# people-counter-74xx.net
KiCad netlist of a schematic drawn in EAGLE
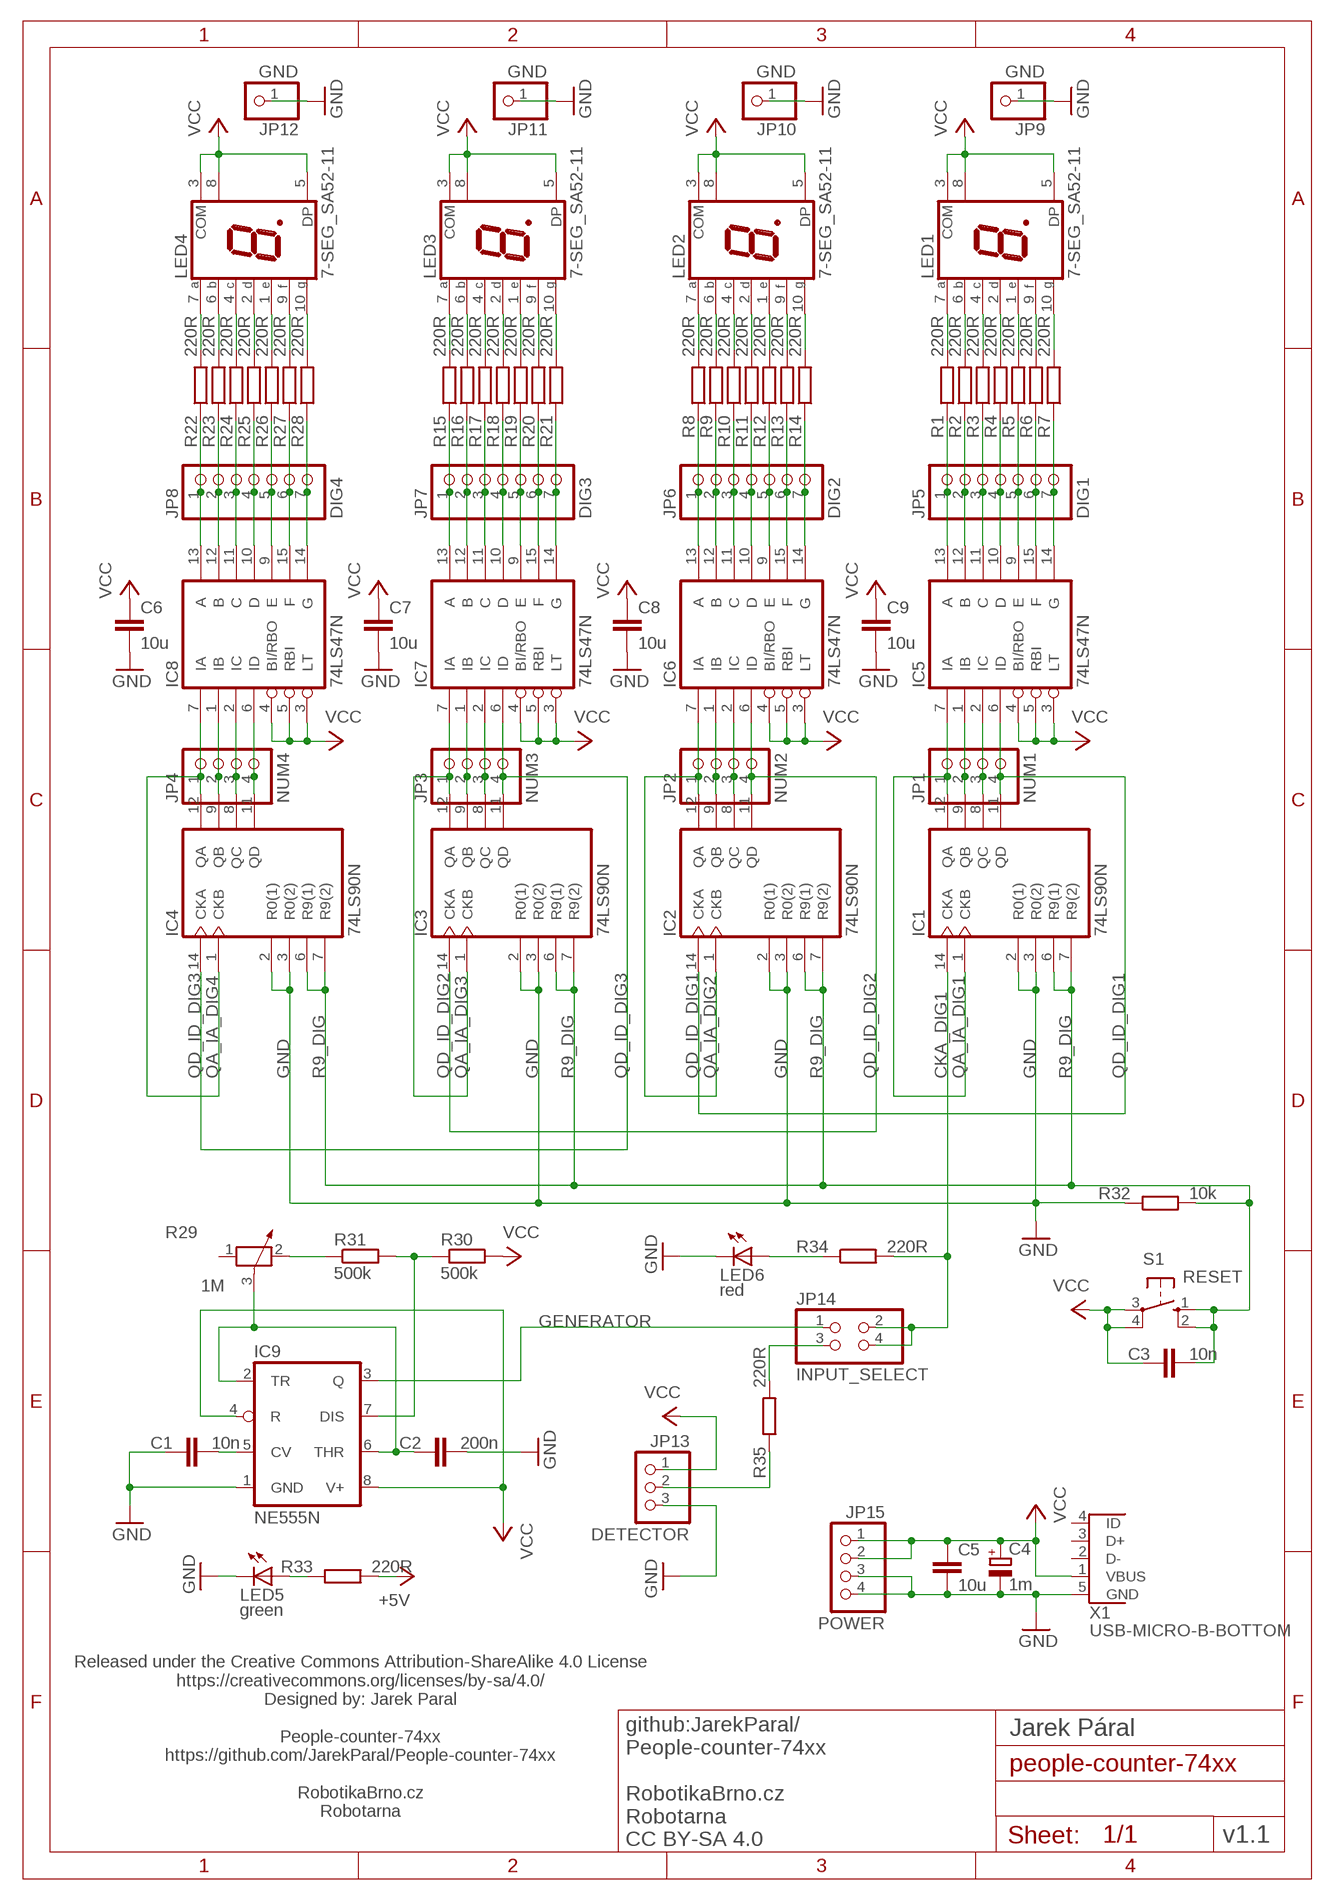
[diagram p0: schematic, sheet 1]

(export (version "E")
  (design (tool "Eeschema 10.0.6"))
  (components
    (comp (ref "C1")
      (value "10n")
      (footprint "eagle-import:C0603")
      (libsource (lib "eagle-import") (part "C-EUC0603"))
    )
    (comp (ref "C2")
      (value "200n")
      (footprint "eagle-import:C0805")
      (libsource (lib "eagle-import") (part "C-EUC0805"))
    )
    (comp (ref "C3")
      (value "10n")
      (footprint "eagle-import:C0603")
      (libsource (lib "eagle-import") (part "C-EUC0603"))
    )
    (comp (ref "C4")
      (value "1m")
      (footprint "eagle-import:E5-10,5")
      (libsource (lib "eagle-import") (part "CPOL-EUE5-10.5"))
    )
    (comp (ref "C5")
      (value "10u")
      (footprint "eagle-import:C0805")
      (libsource (lib "eagle-import") (part "C-EUC0805"))
    )
    (comp (ref "C6")
      (value "10u")
      (footprint "eagle-import:C0805")
      (libsource (lib "eagle-import") (part "C-EUC0805"))
    )
    (comp (ref "C7")
      (value "10u")
      (footprint "eagle-import:C0805")
      (libsource (lib "eagle-import") (part "C-EUC0805"))
    )
    (comp (ref "C8")
      (value "10u")
      (footprint "eagle-import:C0805")
      (libsource (lib "eagle-import") (part "C-EUC0805"))
    )
    (comp (ref "C9")
      (value "10u")
      (footprint "eagle-import:C0805")
      (libsource (lib "eagle-import") (part "C-EUC0805"))
    )
    (comp (ref "IC1")
      (value "74LS90N")
      (footprint "eagle-import:DIL14")
      (libsource (lib "eagle-import") (part "7490NLS"))
    )
    (comp (ref "IC2")
      (value "74LS90N")
      (footprint "eagle-import:DIL14")
      (libsource (lib "eagle-import") (part "7490NLS"))
    )
    (comp (ref "IC3")
      (value "74LS90N")
      (footprint "eagle-import:DIL14")
      (libsource (lib "eagle-import") (part "7490NLS"))
    )
    (comp (ref "IC4")
      (value "74LS90N")
      (footprint "eagle-import:DIL14")
      (libsource (lib "eagle-import") (part "7490NLS"))
    )
    (comp (ref "IC5")
      (value "74LS47N")
      (footprint "eagle-import:DIL16")
      (libsource (lib "eagle-import") (part "7447NLS"))
    )
    (comp (ref "IC6")
      (value "74LS47N")
      (footprint "eagle-import:DIL16")
      (libsource (lib "eagle-import") (part "7447NLS"))
    )
    (comp (ref "IC7")
      (value "74LS47N")
      (footprint "eagle-import:DIL16")
      (libsource (lib "eagle-import") (part "7447NLS"))
    )
    (comp (ref "IC8")
      (value "74LS47N")
      (footprint "eagle-import:DIL16")
      (libsource (lib "eagle-import") (part "7447NLS"))
    )
    (comp (ref "IC9")
      (value "NE555N")
      (footprint "eagle-import:DIL08")
      (libsource (lib "eagle-import") (part "555NNE"))
    )
    (comp (ref "JP1")
      (value "NUM1")
      (footprint "eagle-import:1X04")
      (libsource (lib "eagle-import") (part "PINHD-1X4"))
    )
    (comp (ref "JP2")
      (value "NUM2")
      (footprint "eagle-import:1X04")
      (libsource (lib "eagle-import") (part "PINHD-1X4"))
    )
    (comp (ref "JP3")
      (value "NUM3")
      (footprint "eagle-import:1X04")
      (libsource (lib "eagle-import") (part "PINHD-1X4"))
    )
    (comp (ref "JP4")
      (value "NUM4")
      (footprint "eagle-import:1X04")
      (libsource (lib "eagle-import") (part "PINHD-1X4"))
    )
    (comp (ref "JP5")
      (value "DIG1")
      (footprint "eagle-import:1X07")
      (libsource (lib "eagle-import") (part "PINHD-1X7"))
    )
    (comp (ref "JP6")
      (value "DIG2")
      (footprint "eagle-import:1X07")
      (libsource (lib "eagle-import") (part "PINHD-1X7"))
    )
    (comp (ref "JP7")
      (value "DIG3")
      (footprint "eagle-import:1X07")
      (libsource (lib "eagle-import") (part "PINHD-1X7"))
    )
    (comp (ref "JP8")
      (value "DIG4")
      (footprint "eagle-import:1X07")
      (libsource (lib "eagle-import") (part "PINHD-1X7"))
    )
    (comp (ref "JP9")
      (value "GND")
      (footprint "eagle-import:1X01")
      (libsource (lib "eagle-import") (part "PINHD-1X1"))
    )
    (comp (ref "JP10")
      (value "GND")
      (footprint "eagle-import:1X01")
      (libsource (lib "eagle-import") (part "PINHD-1X1"))
    )
    (comp (ref "JP11")
      (value "GND")
      (footprint "eagle-import:1X01")
      (libsource (lib "eagle-import") (part "PINHD-1X1"))
    )
    (comp (ref "JP12")
      (value "GND")
      (footprint "eagle-import:1X01")
      (libsource (lib "eagle-import") (part "PINHD-1X1"))
    )
    (comp (ref "JP13")
      (value "DETECTOR")
      (footprint "eagle-import:1X03_90")
      (libsource (lib "eagle-import") (part "PINHD-1X3/90"))
    )
    (comp (ref "JP14")
      (value "INPUT_SELECT")
      (footprint "eagle-import:2X02")
      (libsource (lib "eagle-import") (part "PINHD-2X2"))
    )
    (comp (ref "JP15")
      (value "POWER")
      (footprint "eagle-import:1X04_90")
      (libsource (lib "eagle-import") (part "PINHD-1X4/90"))
    )
    (comp (ref "LED1")
      (value "7-SEG_SA52-11")
      (footprint "eagle-import:SA52-11")
      (libsource (lib "eagle-import") (part "7-SEG_SA52-11"))
    )
    (comp (ref "LED2")
      (value "7-SEG_SA52-11")
      (footprint "eagle-import:SA52-11")
      (libsource (lib "eagle-import") (part "7-SEG_SA52-11"))
    )
    (comp (ref "LED3")
      (value "7-SEG_SA52-11")
      (footprint "eagle-import:SA52-11")
      (libsource (lib "eagle-import") (part "7-SEG_SA52-11"))
    )
    (comp (ref "LED4")
      (value "7-SEG_SA52-11")
      (footprint "eagle-import:SA52-11")
      (libsource (lib "eagle-import") (part "7-SEG_SA52-11"))
    )
    (comp (ref "LED5")
      (value "green")
      (footprint "eagle-import:CHIPLED_0603")
      (libsource (lib "eagle-import") (part "LEDCHIPLED_0603"))
    )
    (comp (ref "LED6")
      (value "red")
      (footprint "eagle-import:CHIPLED_0603")
      (libsource (lib "eagle-import") (part "LEDCHIPLED_0603"))
    )
    (comp (ref "R1")
      (value "220R")
      (footprint "eagle-import:R0603")
      (libsource (lib "eagle-import") (part "R-EU_R0603"))
    )
    (comp (ref "R2")
      (value "220R")
      (footprint "eagle-import:R0603")
      (libsource (lib "eagle-import") (part "R-EU_R0603"))
    )
    (comp (ref "R3")
      (value "220R")
      (footprint "eagle-import:R0603")
      (libsource (lib "eagle-import") (part "R-EU_R0603"))
    )
    (comp (ref "R4")
      (value "220R")
      (footprint "eagle-import:R0603")
      (libsource (lib "eagle-import") (part "R-EU_R0603"))
    )
    (comp (ref "R5")
      (value "220R")
      (footprint "eagle-import:R0603")
      (libsource (lib "eagle-import") (part "R-EU_R0603"))
    )
    (comp (ref "R6")
      (value "220R")
      (footprint "eagle-import:R0603")
      (libsource (lib "eagle-import") (part "R-EU_R0603"))
    )
    (comp (ref "R7")
      (value "220R")
      (footprint "eagle-import:R0603")
      (libsource (lib "eagle-import") (part "R-EU_R0603"))
    )
    (comp (ref "R8")
      (value "220R")
      (footprint "eagle-import:R0603")
      (libsource (lib "eagle-import") (part "R-EU_R0603"))
    )
    (comp (ref "R9")
      (value "220R")
      (footprint "eagle-import:R0603")
      (libsource (lib "eagle-import") (part "R-EU_R0603"))
    )
    (comp (ref "R10")
      (value "220R")
      (footprint "eagle-import:R0603")
      (libsource (lib "eagle-import") (part "R-EU_R0603"))
    )
    (comp (ref "R11")
      (value "220R")
      (footprint "eagle-import:R0603")
      (libsource (lib "eagle-import") (part "R-EU_R0603"))
    )
    (comp (ref "R12")
      (value "220R")
      (footprint "eagle-import:R0603")
      (libsource (lib "eagle-import") (part "R-EU_R0603"))
    )
    (comp (ref "R13")
      (value "220R")
      (footprint "eagle-import:R0603")
      (libsource (lib "eagle-import") (part "R-EU_R0603"))
    )
    (comp (ref "R14")
      (value "220R")
      (footprint "eagle-import:R0603")
      (libsource (lib "eagle-import") (part "R-EU_R0603"))
    )
    (comp (ref "R15")
      (value "220R")
      (footprint "eagle-import:R0603")
      (libsource (lib "eagle-import") (part "R-EU_R0603"))
    )
    (comp (ref "R16")
      (value "220R")
      (footprint "eagle-import:R0603")
      (libsource (lib "eagle-import") (part "R-EU_R0603"))
    )
    (comp (ref "R17")
      (value "220R")
      (footprint "eagle-import:R0603")
      (libsource (lib "eagle-import") (part "R-EU_R0603"))
    )
    (comp (ref "R18")
      (value "220R")
      (footprint "eagle-import:R0603")
      (libsource (lib "eagle-import") (part "R-EU_R0603"))
    )
    (comp (ref "R19")
      (value "220R")
      (footprint "eagle-import:R0603")
      (libsource (lib "eagle-import") (part "R-EU_R0603"))
    )
    (comp (ref "R20")
      (value "220R")
      (footprint "eagle-import:R0603")
      (libsource (lib "eagle-import") (part "R-EU_R0603"))
    )
    (comp (ref "R21")
      (value "220R")
      (footprint "eagle-import:R0603")
      (libsource (lib "eagle-import") (part "R-EU_R0603"))
    )
    (comp (ref "R22")
      (value "220R")
      (footprint "eagle-import:R0603")
      (libsource (lib "eagle-import") (part "R-EU_R0603"))
    )
    (comp (ref "R23")
      (value "220R")
      (footprint "eagle-import:R0603")
      (libsource (lib "eagle-import") (part "R-EU_R0603"))
    )
    (comp (ref "R24")
      (value "220R")
      (footprint "eagle-import:R0603")
      (libsource (lib "eagle-import") (part "R-EU_R0603"))
    )
    (comp (ref "R25")
      (value "220R")
      (footprint "eagle-import:R0603")
      (libsource (lib "eagle-import") (part "R-EU_R0603"))
    )
    (comp (ref "R26")
      (value "220R")
      (footprint "eagle-import:R0603")
      (libsource (lib "eagle-import") (part "R-EU_R0603"))
    )
    (comp (ref "R27")
      (value "220R")
      (footprint "eagle-import:R0603")
      (libsource (lib "eagle-import") (part "R-EU_R0603"))
    )
    (comp (ref "R28")
      (value "220R")
      (footprint "eagle-import:R0603")
      (libsource (lib "eagle-import") (part "R-EU_R0603"))
    )
    (comp (ref "R29")
      (value "1M")
      (footprint "eagle-import:PT-10")
      (libsource (lib "eagle-import") (part "POTENTIOMETER_PT-10"))
    )
    (comp (ref "R30")
      (value "500k")
      (footprint "eagle-import:R0603")
      (libsource (lib "eagle-import") (part "R-EU_R0603"))
    )
    (comp (ref "R31")
      (value "500k")
      (footprint "eagle-import:R0603")
      (libsource (lib "eagle-import") (part "R-EU_R0603"))
    )
    (comp (ref "R32")
      (value "10k")
      (footprint "eagle-import:R0603")
      (libsource (lib "eagle-import") (part "R-EU_R0603"))
    )
    (comp (ref "R33")
      (value "220R")
      (footprint "eagle-import:R0603")
      (libsource (lib "eagle-import") (part "R-EU_R0603"))
    )
    (comp (ref "R34")
      (value "220R")
      (footprint "eagle-import:R0603")
      (libsource (lib "eagle-import") (part "R-EU_R0603"))
    )
    (comp (ref "R35")
      (value "220R")
      (footprint "eagle-import:R0603")
      (libsource (lib "eagle-import") (part "R-EU_R0603"))
    )
    (comp (ref "S1")
      (value "RESET")
      (footprint "eagle-import:B3F-10XX")
      (fields (field (name "MPN") "B3F-1000"))
      (libsource (lib "eagle-import") (part "10-XX"))
    )
    (comp (ref "X1")
      (value "USB-MICRO-B-BOTTOM")
      (footprint "eagle-import:USB-MICRO-B-BOTTOM-MOLEX")
      (libsource (lib "eagle-import") (part "USB-MICRO-B-BOTTOM"))
    )
  )
  (nets
    (net (code "1") (name "+5V") (class "Default")
      (node (ref "R33") (pin "2") (pinfunction "2_2") (pintype "passive"))
    )
    (net (code "2") (name "/CKA_DIG1") (class "Default")
      (node (ref "IC1") (pin "14") (pinfunction "CKA_14") (pintype "input"))
      (node (ref "JP14") (pin "2") (pinfunction "2_2") (pintype "passive"))
      (node (ref "JP14") (pin "4") (pinfunction "4_4") (pintype "passive"))
      (node (ref "R34") (pin "2") (pinfunction "2_2") (pintype "passive"))
    )
    (net (code "3") (name "/GENERATOR") (class "Default")
      (node (ref "IC9") (pin "3") (pinfunction "Q_3") (pintype "output"))
      (node (ref "JP14") (pin "1") (pinfunction "1_1") (pintype "passive"))
    )
    (net (code "4") (name "/QA_IA_DIG1") (class "Default")
      (node (ref "IC1") (pin "1") (pinfunction "CKB_1") (pintype "input"))
      (node (ref "IC1") (pin "12") (pinfunction "QA_12") (pintype "output"))
      (node (ref "IC5") (pin "7") (pinfunction "IA_7") (pintype "input"))
      (node (ref "JP1") (pin "1") (pinfunction "1_1") (pintype "passive"))
    )
    (net (code "5") (name "/QA_IA_DIG2") (class "Default")
      (node (ref "IC2") (pin "1") (pinfunction "CKB_1") (pintype "input"))
      (node (ref "IC2") (pin "12") (pinfunction "QA_12") (pintype "output"))
      (node (ref "IC6") (pin "7") (pinfunction "IA_7") (pintype "input"))
      (node (ref "JP2") (pin "1") (pinfunction "1_1") (pintype "passive"))
    )
    (net (code "6") (name "/QA_IA_DIG3") (class "Default")
      (node (ref "IC3") (pin "1") (pinfunction "CKB_1") (pintype "input"))
      (node (ref "IC3") (pin "12") (pinfunction "QA_12") (pintype "output"))
      (node (ref "IC7") (pin "7") (pinfunction "IA_7") (pintype "input"))
      (node (ref "JP3") (pin "1") (pinfunction "1_1") (pintype "passive"))
    )
    (net (code "7") (name "/QA_IA_DIG4") (class "Default")
      (node (ref "IC4") (pin "1") (pinfunction "CKB_1") (pintype "input"))
      (node (ref "IC4") (pin "12") (pinfunction "QA_12") (pintype "output"))
      (node (ref "IC8") (pin "7") (pinfunction "IA_7") (pintype "input"))
      (node (ref "JP4") (pin "1") (pinfunction "1_1") (pintype "passive"))
    )
    (net (code "8") (name "/QD_ID_DIG1") (class "Default")
      (node (ref "IC1") (pin "11") (pinfunction "QD_11") (pintype "output"))
      (node (ref "IC2") (pin "14") (pinfunction "CKA_14") (pintype "input"))
      (node (ref "IC5") (pin "6") (pinfunction "ID_6") (pintype "input"))
      (node (ref "JP1") (pin "4") (pinfunction "4_4") (pintype "passive"))
    )
    (net (code "9") (name "/QD_ID_DIG2") (class "Default")
      (node (ref "IC2") (pin "11") (pinfunction "QD_11") (pintype "output"))
      (node (ref "IC3") (pin "14") (pinfunction "CKA_14") (pintype "input"))
      (node (ref "IC6") (pin "6") (pinfunction "ID_6") (pintype "input"))
      (node (ref "JP2") (pin "4") (pinfunction "4_4") (pintype "passive"))
    )
    (net (code "10") (name "/QD_ID_DIG3") (class "Default")
      (node (ref "IC3") (pin "11") (pinfunction "QD_11") (pintype "output"))
      (node (ref "IC4") (pin "14") (pinfunction "CKA_14") (pintype "input"))
      (node (ref "IC7") (pin "6") (pinfunction "ID_6") (pintype "input"))
      (node (ref "JP3") (pin "4") (pinfunction "4_4") (pintype "passive"))
    )
    (net (code "11") (name "/R9_DIG") (class "Default")
      (node (ref "C3") (pin "2") (pinfunction "2_2") (pintype "passive"))
      (node (ref "IC1") (pin "6") (pinfunction "R9(1)_6") (pintype "input"))
      (node (ref "IC1") (pin "7") (pinfunction "R9(2)_7") (pintype "input"))
      (node (ref "IC2") (pin "6") (pinfunction "R9(1)_6") (pintype "input"))
      (node (ref "IC2") (pin "7") (pinfunction "R9(2)_7") (pintype "input"))
      (node (ref "IC3") (pin "6") (pinfunction "R9(1)_6") (pintype "input"))
      (node (ref "IC3") (pin "7") (pinfunction "R9(2)_7") (pintype "input"))
      (node (ref "IC4") (pin "6") (pinfunction "R9(1)_6") (pintype "input"))
      (node (ref "IC4") (pin "7") (pinfunction "R9(2)_7") (pintype "input"))
      (node (ref "R32") (pin "2") (pinfunction "2_2") (pintype "passive"))
      (node (ref "S1") (pin "1") (pinfunction "S_1") (pintype "passive"))
      (node (ref "S1") (pin "2") (pinfunction "S1_2") (pintype "passive"))
    )
    (net (code "12") (name "GND") (class "Default")
      (node (ref "C1") (pin "1") (pinfunction "1_1") (pintype "passive"))
      (node (ref "C2") (pin "2") (pinfunction "2_2") (pintype "passive"))
      (node (ref "C4") (pin "-") (pinfunction "-_-") (pintype "passive"))
      (node (ref "C5") (pin "2") (pinfunction "2_2") (pintype "passive"))
      (node (ref "C6") (pin "2") (pinfunction "2_2") (pintype "passive"))
      (node (ref "C7") (pin "2") (pinfunction "2_2") (pintype "passive"))
      (node (ref "C8") (pin "2") (pinfunction "2_2") (pintype "passive"))
      (node (ref "C9") (pin "2") (pinfunction "2_2") (pintype "passive"))
      (node (ref "IC1") (pin "2") (pinfunction "R0(1)_2") (pintype "input"))
      (node (ref "IC1") (pin "3") (pinfunction "R0(2)_3") (pintype "input"))
      (node (ref "IC2") (pin "2") (pinfunction "R0(1)_2") (pintype "input"))
      (node (ref "IC2") (pin "3") (pinfunction "R0(2)_3") (pintype "input"))
      (node (ref "IC3") (pin "2") (pinfunction "R0(1)_2") (pintype "input"))
      (node (ref "IC3") (pin "3") (pinfunction "R0(2)_3") (pintype "input"))
      (node (ref "IC4") (pin "2") (pinfunction "R0(1)_2") (pintype "input"))
      (node (ref "IC4") (pin "3") (pinfunction "R0(2)_3") (pintype "input"))
      (node (ref "IC9") (pin "1") (pinfunction "GND_1") (pintype "power_in"))
      (node (ref "JP10") (pin "1") (pinfunction "1_1") (pintype "passive"))
      (node (ref "JP11") (pin "1") (pinfunction "1_1") (pintype "passive"))
      (node (ref "JP12") (pin "1") (pinfunction "1_1") (pintype "passive"))
      (node (ref "JP13") (pin "3") (pinfunction "3_3") (pintype "passive"))
      (node (ref "JP15") (pin "3") (pinfunction "3_3") (pintype "passive"))
      (node (ref "JP15") (pin "4") (pinfunction "4_4") (pintype "passive"))
      (node (ref "JP9") (pin "1") (pinfunction "1_1") (pintype "passive"))
      (node (ref "LED5") (pin "C") (pinfunction "C_C") (pintype "passive"))
      (node (ref "LED6") (pin "C") (pinfunction "C_C") (pintype "passive"))
      (node (ref "R32") (pin "1") (pinfunction "1_1") (pintype "passive"))
      (node (ref "X1") (pin "5") (pinfunction "GND_5") (pintype "passive"))
    )
    (net (code "13") (name "Net-(IC1A-QB)") (class "Default")
      (node (ref "IC1") (pin "9") (pinfunction "QB_9") (pintype "output"))
      (node (ref "IC5") (pin "1") (pinfunction "IB_1") (pintype "input"))
      (node (ref "JP1") (pin "2") (pinfunction "2_2") (pintype "passive"))
    )
    (net (code "14") (name "Net-(IC1A-QC)") (class "Default")
      (node (ref "IC1") (pin "8") (pinfunction "QC_8") (pintype "output"))
      (node (ref "IC5") (pin "2") (pinfunction "IC_2") (pintype "input"))
      (node (ref "JP1") (pin "3") (pinfunction "3_3") (pintype "passive"))
    )
    (net (code "15") (name "Net-(IC2A-QB)") (class "Default")
      (node (ref "IC2") (pin "9") (pinfunction "QB_9") (pintype "output"))
      (node (ref "IC6") (pin "1") (pinfunction "IB_1") (pintype "input"))
      (node (ref "JP2") (pin "2") (pinfunction "2_2") (pintype "passive"))
    )
    (net (code "16") (name "Net-(IC2A-QC)") (class "Default")
      (node (ref "IC2") (pin "8") (pinfunction "QC_8") (pintype "output"))
      (node (ref "IC6") (pin "2") (pinfunction "IC_2") (pintype "input"))
      (node (ref "JP2") (pin "3") (pinfunction "3_3") (pintype "passive"))
    )
    (net (code "17") (name "Net-(IC3A-QB)") (class "Default")
      (node (ref "IC3") (pin "9") (pinfunction "QB_9") (pintype "output"))
      (node (ref "IC7") (pin "1") (pinfunction "IB_1") (pintype "input"))
      (node (ref "JP3") (pin "2") (pinfunction "2_2") (pintype "passive"))
    )
    (net (code "18") (name "Net-(IC3A-QC)") (class "Default")
      (node (ref "IC3") (pin "8") (pinfunction "QC_8") (pintype "output"))
      (node (ref "IC7") (pin "2") (pinfunction "IC_2") (pintype "input"))
      (node (ref "JP3") (pin "3") (pinfunction "3_3") (pintype "passive"))
    )
    (net (code "19") (name "Net-(IC4A-QB)") (class "Default")
      (node (ref "IC4") (pin "9") (pinfunction "QB_9") (pintype "output"))
      (node (ref "IC8") (pin "1") (pinfunction "IB_1") (pintype "input"))
      (node (ref "JP4") (pin "2") (pinfunction "2_2") (pintype "passive"))
    )
    (net (code "20") (name "Net-(IC4A-QC)") (class "Default")
      (node (ref "IC4") (pin "8") (pinfunction "QC_8") (pintype "output"))
      (node (ref "IC8") (pin "2") (pinfunction "IC_2") (pintype "input"))
      (node (ref "JP4") (pin "3") (pinfunction "3_3") (pintype "passive"))
    )
    (net (code "21") (name "Net-(IC4A-QD)") (class "Default")
      (node (ref "IC4") (pin "11") (pinfunction "QD_11") (pintype "output"))
      (node (ref "IC8") (pin "6") (pinfunction "ID_6") (pintype "input"))
      (node (ref "JP4") (pin "4") (pinfunction "4_4") (pintype "passive"))
    )
    (net (code "22") (name "Net-(IC5A-A)") (class "Default")
      (node (ref "IC5") (pin "13") (pinfunction "A_13") (pintype "output"))
      (node (ref "JP5") (pin "1") (pinfunction "1_1") (pintype "passive"))
      (node (ref "R1") (pin "1") (pinfunction "1_1") (pintype "passive"))
    )
    (net (code "23") (name "Net-(IC5A-B)") (class "Default")
      (node (ref "IC5") (pin "12") (pinfunction "B_12") (pintype "output"))
      (node (ref "JP5") (pin "2") (pinfunction "2_2") (pintype "passive"))
      (node (ref "R2") (pin "1") (pinfunction "1_1") (pintype "passive"))
    )
    (net (code "24") (name "Net-(IC5A-C)") (class "Default")
      (node (ref "IC5") (pin "11") (pinfunction "C_11") (pintype "output"))
      (node (ref "JP5") (pin "3") (pinfunction "3_3") (pintype "passive"))
      (node (ref "R3") (pin "1") (pinfunction "1_1") (pintype "passive"))
    )
    (net (code "25") (name "Net-(IC5A-D)") (class "Default")
      (node (ref "IC5") (pin "10") (pinfunction "D_10") (pintype "output"))
      (node (ref "JP5") (pin "4") (pinfunction "4_4") (pintype "passive"))
      (node (ref "R4") (pin "1") (pinfunction "1_1") (pintype "passive"))
    )
    (net (code "26") (name "Net-(IC5A-E)") (class "Default")
      (node (ref "IC5") (pin "9") (pinfunction "E_9") (pintype "output"))
      (node (ref "JP5") (pin "5") (pinfunction "5_5") (pintype "passive"))
      (node (ref "R5") (pin "1") (pinfunction "1_1") (pintype "passive"))
    )
    (net (code "27") (name "Net-(IC5A-F)") (class "Default")
      (node (ref "IC5") (pin "15") (pinfunction "F_15") (pintype "output"))
      (node (ref "JP5") (pin "6") (pinfunction "6_6") (pintype "passive"))
      (node (ref "R6") (pin "1") (pinfunction "1_1") (pintype "passive"))
    )
    (net (code "28") (name "Net-(IC5A-G)") (class "Default")
      (node (ref "IC5") (pin "14") (pinfunction "G_14") (pintype "output"))
      (node (ref "JP5") (pin "7") (pinfunction "7_7") (pintype "passive"))
      (node (ref "R7") (pin "1") (pinfunction "1_1") (pintype "passive"))
    )
    (net (code "29") (name "Net-(IC6A-A)") (class "Default")
      (node (ref "IC6") (pin "13") (pinfunction "A_13") (pintype "output"))
      (node (ref "JP6") (pin "1") (pinfunction "1_1") (pintype "passive"))
      (node (ref "R8") (pin "1") (pinfunction "1_1") (pintype "passive"))
    )
    (net (code "30") (name "Net-(IC6A-B)") (class "Default")
      (node (ref "IC6") (pin "12") (pinfunction "B_12") (pintype "output"))
      (node (ref "JP6") (pin "2") (pinfunction "2_2") (pintype "passive"))
      (node (ref "R9") (pin "1") (pinfunction "1_1") (pintype "passive"))
    )
    (net (code "31") (name "Net-(IC6A-C)") (class "Default")
      (node (ref "IC6") (pin "11") (pinfunction "C_11") (pintype "output"))
      (node (ref "JP6") (pin "3") (pinfunction "3_3") (pintype "passive"))
      (node (ref "R10") (pin "1") (pinfunction "1_1") (pintype "passive"))
    )
    (net (code "32") (name "Net-(IC6A-D)") (class "Default")
      (node (ref "IC6") (pin "10") (pinfunction "D_10") (pintype "output"))
      (node (ref "JP6") (pin "4") (pinfunction "4_4") (pintype "passive"))
      (node (ref "R11") (pin "1") (pinfunction "1_1") (pintype "passive"))
    )
    (net (code "33") (name "Net-(IC6A-E)") (class "Default")
      (node (ref "IC6") (pin "9") (pinfunction "E_9") (pintype "output"))
      (node (ref "JP6") (pin "5") (pinfunction "5_5") (pintype "passive"))
      (node (ref "R12") (pin "1") (pinfunction "1_1") (pintype "passive"))
    )
    (net (code "34") (name "Net-(IC6A-F)") (class "Default")
      (node (ref "IC6") (pin "15") (pinfunction "F_15") (pintype "output"))
      (node (ref "JP6") (pin "6") (pinfunction "6_6") (pintype "passive"))
      (node (ref "R13") (pin "1") (pinfunction "1_1") (pintype "passive"))
    )
    (net (code "35") (name "Net-(IC6A-G)") (class "Default")
      (node (ref "IC6") (pin "14") (pinfunction "G_14") (pintype "output"))
      (node (ref "JP6") (pin "7") (pinfunction "7_7") (pintype "passive"))
      (node (ref "R14") (pin "1") (pinfunction "1_1") (pintype "passive"))
    )
    (net (code "36") (name "Net-(IC7A-A)") (class "Default")
      (node (ref "IC7") (pin "13") (pinfunction "A_13") (pintype "output"))
      (node (ref "JP7") (pin "1") (pinfunction "1_1") (pintype "passive"))
      (node (ref "R15") (pin "1") (pinfunction "1_1") (pintype "passive"))
    )
    (net (code "37") (name "Net-(IC7A-B)") (class "Default")
      (node (ref "IC7") (pin "12") (pinfunction "B_12") (pintype "output"))
      (node (ref "JP7") (pin "2") (pinfunction "2_2") (pintype "passive"))
      (node (ref "R16") (pin "1") (pinfunction "1_1") (pintype "passive"))
    )
    (net (code "38") (name "Net-(IC7A-C)") (class "Default")
      (node (ref "IC7") (pin "11") (pinfunction "C_11") (pintype "output"))
      (node (ref "JP7") (pin "3") (pinfunction "3_3") (pintype "passive"))
      (node (ref "R17") (pin "1") (pinfunction "1_1") (pintype "passive"))
    )
    (net (code "39") (name "Net-(IC7A-D)") (class "Default")
      (node (ref "IC7") (pin "10") (pinfunction "D_10") (pintype "output"))
      (node (ref "JP7") (pin "4") (pinfunction "4_4") (pintype "passive"))
      (node (ref "R18") (pin "1") (pinfunction "1_1") (pintype "passive"))
    )
    (net (code "40") (name "Net-(IC7A-E)") (class "Default")
      (node (ref "IC7") (pin "9") (pinfunction "E_9") (pintype "output"))
      (node (ref "JP7") (pin "5") (pinfunction "5_5") (pintype "passive"))
      (node (ref "R19") (pin "1") (pinfunction "1_1") (pintype "passive"))
    )
    (net (code "41") (name "Net-(IC7A-F)") (class "Default")
      (node (ref "IC7") (pin "15") (pinfunction "F_15") (pintype "output"))
      (node (ref "JP7") (pin "6") (pinfunction "6_6") (pintype "passive"))
      (node (ref "R20") (pin "1") (pinfunction "1_1") (pintype "passive"))
    )
    (net (code "42") (name "Net-(IC7A-G)") (class "Default")
      (node (ref "IC7") (pin "14") (pinfunction "G_14") (pintype "output"))
      (node (ref "JP7") (pin "7") (pinfunction "7_7") (pintype "passive"))
      (node (ref "R21") (pin "1") (pinfunction "1_1") (pintype "passive"))
    )
    (net (code "43") (name "Net-(IC8A-A)") (class "Default")
      (node (ref "IC8") (pin "13") (pinfunction "A_13") (pintype "output"))
      (node (ref "JP8") (pin "1") (pinfunction "1_1") (pintype "passive"))
      (node (ref "R22") (pin "1") (pinfunction "1_1") (pintype "passive"))
    )
    (net (code "44") (name "Net-(IC8A-B)") (class "Default")
      (node (ref "IC8") (pin "12") (pinfunction "B_12") (pintype "output"))
      (node (ref "JP8") (pin "2") (pinfunction "2_2") (pintype "passive"))
      (node (ref "R23") (pin "1") (pinfunction "1_1") (pintype "passive"))
    )
    (net (code "45") (name "Net-(IC8A-C)") (class "Default")
      (node (ref "IC8") (pin "11") (pinfunction "C_11") (pintype "output"))
      (node (ref "JP8") (pin "3") (pinfunction "3_3") (pintype "passive"))
      (node (ref "R24") (pin "1") (pinfunction "1_1") (pintype "passive"))
    )
    (net (code "46") (name "Net-(IC8A-D)") (class "Default")
      (node (ref "IC8") (pin "10") (pinfunction "D_10") (pintype "output"))
      (node (ref "JP8") (pin "4") (pinfunction "4_4") (pintype "passive"))
      (node (ref "R25") (pin "1") (pinfunction "1_1") (pintype "passive"))
    )
    (net (code "47") (name "Net-(IC8A-E)") (class "Default")
      (node (ref "IC8") (pin "9") (pinfunction "E_9") (pintype "output"))
      (node (ref "JP8") (pin "5") (pinfunction "5_5") (pintype "passive"))
      (node (ref "R26") (pin "1") (pinfunction "1_1") (pintype "passive"))
    )
    (net (code "48") (name "Net-(IC8A-F)") (class "Default")
      (node (ref "IC8") (pin "15") (pinfunction "F_15") (pintype "output"))
      (node (ref "JP8") (pin "6") (pinfunction "6_6") (pintype "passive"))
      (node (ref "R27") (pin "1") (pinfunction "1_1") (pintype "passive"))
    )
    (net (code "49") (name "Net-(IC8A-G)") (class "Default")
      (node (ref "IC8") (pin "14") (pinfunction "G_14") (pintype "output"))
      (node (ref "JP8") (pin "7") (pinfunction "7_7") (pintype "passive"))
      (node (ref "R28") (pin "1") (pinfunction "1_1") (pintype "passive"))
    )
    (net (code "50") (name "Net-(IC9-CV)") (class "Default")
      (node (ref "C1") (pin "2") (pinfunction "2_2") (pintype "passive"))
      (node (ref "IC9") (pin "5") (pinfunction "CV_5") (pintype "input"))
    )
    (net (code "51") (name "Net-(IC9-DIS)") (class "Default")
      (node (ref "IC9") (pin "7") (pinfunction "DIS_7") (pintype "input"))
      (node (ref "R30") (pin "1") (pinfunction "1_1") (pintype "passive"))
      (node (ref "R31") (pin "2") (pinfunction "2_2") (pintype "passive"))
    )
    (net (code "52") (name "Net-(IC9-THR)") (class "Default")
      (node (ref "C2") (pin "1") (pinfunction "1_1") (pintype "passive"))
      (node (ref "IC9") (pin "2") (pinfunction "TR_2") (pintype "input"))
      (node (ref "IC9") (pin "6") (pinfunction "THR_6") (pintype "input"))
      (node (ref "R29") (pin "3") (pinfunction "3_3") (pintype "passive"))
    )
    (net (code "53") (name "Net-(JP13-Pad2)") (class "Default")
      (node (ref "JP13") (pin "2") (pinfunction "2_2") (pintype "passive"))
      (node (ref "R35") (pin "1") (pinfunction "1_1") (pintype "passive"))
    )
    (net (code "54") (name "Net-(JP14-Pad3)") (class "Default")
      (node (ref "JP14") (pin "3") (pinfunction "3_3") (pintype "passive"))
      (node (ref "R35") (pin "2") (pinfunction "2_2") (pintype "passive"))
    )
    (net (code "55") (name "Net-(LED1-A)") (class "Default")
      (node (ref "LED1") (pin "7") (pinfunction "A_7") (pintype "passive"))
      (node (ref "R1") (pin "2") (pinfunction "2_2") (pintype "passive"))
    )
    (net (code "56") (name "Net-(LED1-B)") (class "Default")
      (node (ref "LED1") (pin "6") (pinfunction "B_6") (pintype "passive"))
      (node (ref "R2") (pin "2") (pinfunction "2_2") (pintype "passive"))
    )
    (net (code "57") (name "Net-(LED1-C)") (class "Default")
      (node (ref "LED1") (pin "4") (pinfunction "C_4") (pintype "passive"))
      (node (ref "R3") (pin "2") (pinfunction "2_2") (pintype "passive"))
    )
    (net (code "58") (name "Net-(LED1-D)") (class "Default")
      (node (ref "LED1") (pin "2") (pinfunction "D_2") (pintype "passive"))
      (node (ref "R4") (pin "2") (pinfunction "2_2") (pintype "passive"))
    )
    (net (code "59") (name "Net-(LED1-E)") (class "Default")
      (node (ref "LED1") (pin "1") (pinfunction "E_1") (pintype "passive"))
      (node (ref "R5") (pin "2") (pinfunction "2_2") (pintype "passive"))
    )
    (net (code "60") (name "Net-(LED1-F)") (class "Default")
      (node (ref "LED1") (pin "9") (pinfunction "F_9") (pintype "passive"))
      (node (ref "R6") (pin "2") (pinfunction "2_2") (pintype "passive"))
    )
    (net (code "61") (name "Net-(LED1-G)") (class "Default")
      (node (ref "LED1") (pin "10") (pinfunction "G_10") (pintype "passive"))
      (node (ref "R7") (pin "2") (pinfunction "2_2") (pintype "passive"))
    )
    (net (code "62") (name "Net-(LED2-A)") (class "Default")
      (node (ref "LED2") (pin "7") (pinfunction "A_7") (pintype "passive"))
      (node (ref "R8") (pin "2") (pinfunction "2_2") (pintype "passive"))
    )
    (net (code "63") (name "Net-(LED2-B)") (class "Default")
      (node (ref "LED2") (pin "6") (pinfunction "B_6") (pintype "passive"))
      (node (ref "R9") (pin "2") (pinfunction "2_2") (pintype "passive"))
    )
    (net (code "64") (name "Net-(LED2-C)") (class "Default")
      (node (ref "LED2") (pin "4") (pinfunction "C_4") (pintype "passive"))
      (node (ref "R10") (pin "2") (pinfunction "2_2") (pintype "passive"))
    )
    (net (code "65") (name "Net-(LED2-D)") (class "Default")
      (node (ref "LED2") (pin "2") (pinfunction "D_2") (pintype "passive"))
      (node (ref "R11") (pin "2") (pinfunction "2_2") (pintype "passive"))
    )
    (net (code "66") (name "Net-(LED2-E)") (class "Default")
      (node (ref "LED2") (pin "1") (pinfunction "E_1") (pintype "passive"))
      (node (ref "R12") (pin "2") (pinfunction "2_2") (pintype "passive"))
    )
    (net (code "67") (name "Net-(LED2-F)") (class "Default")
      (node (ref "LED2") (pin "9") (pinfunction "F_9") (pintype "passive"))
      (node (ref "R13") (pin "2") (pinfunction "2_2") (pintype "passive"))
    )
    (net (code "68") (name "Net-(LED2-G)") (class "Default")
      (node (ref "LED2") (pin "10") (pinfunction "G_10") (pintype "passive"))
      (node (ref "R14") (pin "2") (pinfunction "2_2") (pintype "passive"))
    )
    (net (code "69") (name "Net-(LED3-A)") (class "Default")
      (node (ref "LED3") (pin "7") (pinfunction "A_7") (pintype "passive"))
      (node (ref "R15") (pin "2") (pinfunction "2_2") (pintype "passive"))
    )
    (net (code "70") (name "Net-(LED3-B)") (class "Default")
      (node (ref "LED3") (pin "6") (pinfunction "B_6") (pintype "passive"))
      (node (ref "R16") (pin "2") (pinfunction "2_2") (pintype "passive"))
    )
    (net (code "71") (name "Net-(LED3-C)") (class "Default")
      (node (ref "LED3") (pin "4") (pinfunction "C_4") (pintype "passive"))
      (node (ref "R17") (pin "2") (pinfunction "2_2") (pintype "passive"))
    )
    (net (code "72") (name "Net-(LED3-D)") (class "Default")
      (node (ref "LED3") (pin "2") (pinfunction "D_2") (pintype "passive"))
      (node (ref "R18") (pin "2") (pinfunction "2_2") (pintype "passive"))
    )
    (net (code "73") (name "Net-(LED3-E)") (class "Default")
      (node (ref "LED3") (pin "1") (pinfunction "E_1") (pintype "passive"))
      (node (ref "R19") (pin "2") (pinfunction "2_2") (pintype "passive"))
    )
    (net (code "74") (name "Net-(LED3-F)") (class "Default")
      (node (ref "LED3") (pin "9") (pinfunction "F_9") (pintype "passive"))
      (node (ref "R20") (pin "2") (pinfunction "2_2") (pintype "passive"))
    )
    (net (code "75") (name "Net-(LED3-G)") (class "Default")
      (node (ref "LED3") (pin "10") (pinfunction "G_10") (pintype "passive"))
      (node (ref "R21") (pin "2") (pinfunction "2_2") (pintype "passive"))
    )
    (net (code "76") (name "Net-(LED4-A)") (class "Default")
      (node (ref "LED4") (pin "7") (pinfunction "A_7") (pintype "passive"))
      (node (ref "R22") (pin "2") (pinfunction "2_2") (pintype "passive"))
    )
    (net (code "77") (name "Net-(LED4-B)") (class "Default")
      (node (ref "LED4") (pin "6") (pinfunction "B_6") (pintype "passive"))
      (node (ref "R23") (pin "2") (pinfunction "2_2") (pintype "passive"))
    )
    (net (code "78") (name "Net-(LED4-C)") (class "Default")
      (node (ref "LED4") (pin "4") (pinfunction "C_4") (pintype "passive"))
      (node (ref "R24") (pin "2") (pinfunction "2_2") (pintype "passive"))
    )
    (net (code "79") (name "Net-(LED4-D)") (class "Default")
      (node (ref "LED4") (pin "2") (pinfunction "D_2") (pintype "passive"))
      (node (ref "R25") (pin "2") (pinfunction "2_2") (pintype "passive"))
    )
    (net (code "80") (name "Net-(LED4-E)") (class "Default")
      (node (ref "LED4") (pin "1") (pinfunction "E_1") (pintype "passive"))
      (node (ref "R26") (pin "2") (pinfunction "2_2") (pintype "passive"))
    )
    (net (code "81") (name "Net-(LED4-F)") (class "Default")
      (node (ref "LED4") (pin "9") (pinfunction "F_9") (pintype "passive"))
      (node (ref "R27") (pin "2") (pinfunction "2_2") (pintype "passive"))
    )
    (net (code "82") (name "Net-(LED4-G)") (class "Default")
      (node (ref "LED4") (pin "10") (pinfunction "G_10") (pintype "passive"))
      (node (ref "R28") (pin "2") (pinfunction "2_2") (pintype "passive"))
    )
    (net (code "83") (name "Net-(LED5-PadA)") (class "Default")
      (node (ref "LED5") (pin "A") (pinfunction "A_A") (pintype "passive"))
      (node (ref "R33") (pin "1") (pinfunction "1_1") (pintype "passive"))
    )
    (net (code "84") (name "Net-(LED6-PadA)") (class "Default")
      (node (ref "LED6") (pin "A") (pinfunction "A_A") (pintype "passive"))
      (node (ref "R34") (pin "1") (pinfunction "1_1") (pintype "passive"))
    )
    (net (code "85") (name "Net-(R29-Pad2)") (class "Default")
      (node (ref "R29") (pin "2") (pinfunction "2_2") (pintype "passive"))
      (node (ref "R31") (pin "1") (pinfunction "1_1") (pintype "passive"))
    )
    (net (code "86") (name "VCC") (class "Default")
      (node (ref "C3") (pin "1") (pinfunction "1_1") (pintype "passive"))
      (node (ref "C4") (pin "+") (pinfunction "+_+") (pintype "passive"))
      (node (ref "C5") (pin "1") (pinfunction "1_1") (pintype "passive"))
      (node (ref "C6") (pin "1") (pinfunction "1_1") (pintype "passive"))
      (node (ref "C7") (pin "1") (pinfunction "1_1") (pintype "passive"))
      (node (ref "C8") (pin "1") (pinfunction "1_1") (pintype "passive"))
      (node (ref "C9") (pin "1") (pinfunction "1_1") (pintype "passive"))
      (node (ref "IC5") (pin "3") (pinfunction "LT_3") (pintype "input"))
      (node (ref "IC5") (pin "4") (pinfunction "BI/RBO_4") (pintype "input"))
      (node (ref "IC5") (pin "5") (pinfunction "RBI_5") (pintype "input"))
      (node (ref "IC6") (pin "3") (pinfunction "LT_3") (pintype "input"))
      (node (ref "IC6") (pin "4") (pinfunction "BI/RBO_4") (pintype "input"))
      (node (ref "IC6") (pin "5") (pinfunction "RBI_5") (pintype "input"))
      (node (ref "IC7") (pin "3") (pinfunction "LT_3") (pintype "input"))
      (node (ref "IC7") (pin "4") (pinfunction "BI/RBO_4") (pintype "input"))
      (node (ref "IC7") (pin "5") (pinfunction "RBI_5") (pintype "input"))
      (node (ref "IC8") (pin "3") (pinfunction "LT_3") (pintype "input"))
      (node (ref "IC8") (pin "4") (pinfunction "BI/RBO_4") (pintype "input"))
      (node (ref "IC8") (pin "5") (pinfunction "RBI_5") (pintype "input"))
      (node (ref "IC9") (pin "4") (pinfunction "R_4") (pintype "input"))
      (node (ref "IC9") (pin "8") (pinfunction "V+_8") (pintype "power_in"))
      (node (ref "JP13") (pin "1") (pinfunction "1_1") (pintype "passive"))
      (node (ref "JP15") (pin "1") (pinfunction "1_1") (pintype "passive"))
      (node (ref "JP15") (pin "2") (pinfunction "2_2") (pintype "passive"))
      (node (ref "LED1") (pin "3") (pinfunction "COM_3") (pintype "passive"))
      (node (ref "LED1") (pin "5") (pinfunction "DP_5") (pintype "passive"))
      (node (ref "LED1") (pin "8") (pinfunction "COM_8") (pintype "passive"))
      (node (ref "LED2") (pin "3") (pinfunction "COM_3") (pintype "passive"))
      (node (ref "LED2") (pin "5") (pinfunction "DP_5") (pintype "passive"))
      (node (ref "LED2") (pin "8") (pinfunction "COM_8") (pintype "passive"))
      (node (ref "LED3") (pin "3") (pinfunction "COM_3") (pintype "passive"))
      (node (ref "LED3") (pin "5") (pinfunction "DP_5") (pintype "passive"))
      (node (ref "LED3") (pin "8") (pinfunction "COM_8") (pintype "passive"))
      (node (ref "LED4") (pin "3") (pinfunction "COM_3") (pintype "passive"))
      (node (ref "LED4") (pin "5") (pinfunction "DP_5") (pintype "passive"))
      (node (ref "LED4") (pin "8") (pinfunction "COM_8") (pintype "passive"))
      (node (ref "R30") (pin "2") (pinfunction "2_2") (pintype "passive"))
      (node (ref "S1") (pin "3") (pinfunction "P_3") (pintype "passive"))
      (node (ref "S1") (pin "4") (pinfunction "P1_4") (pintype "passive"))
      (node (ref "X1") (pin "1") (pinfunction "VBUS_1") (pintype "passive"))
    )
    (net (code "87") (name "unconnected-(R29-Pad1)") (class "Default")
      (node (ref "R29") (pin "1") (pinfunction "1_1") (pintype "passive"))
    )
    (net (code "88") (name "unconnected-(X1-D+-Pad3)") (class "Default")
      (node (ref "X1") (pin "3") (pinfunction "D+_3") (pintype "bidirectional"))
    )
    (net (code "89") (name "unconnected-(X1-D--Pad2)") (class "Default")
      (node (ref "X1") (pin "2") (pinfunction "D-_2") (pintype "bidirectional"))
    )
    (net (code "90") (name "unconnected-(X1-ID-Pad4)") (class "Default")
      (node (ref "X1") (pin "4") (pinfunction "ID_4") (pintype "bidirectional"))
    )
  )
)
